# FPGA_Power.net
KiCad netlist of a schematic drawn in Altium Designer
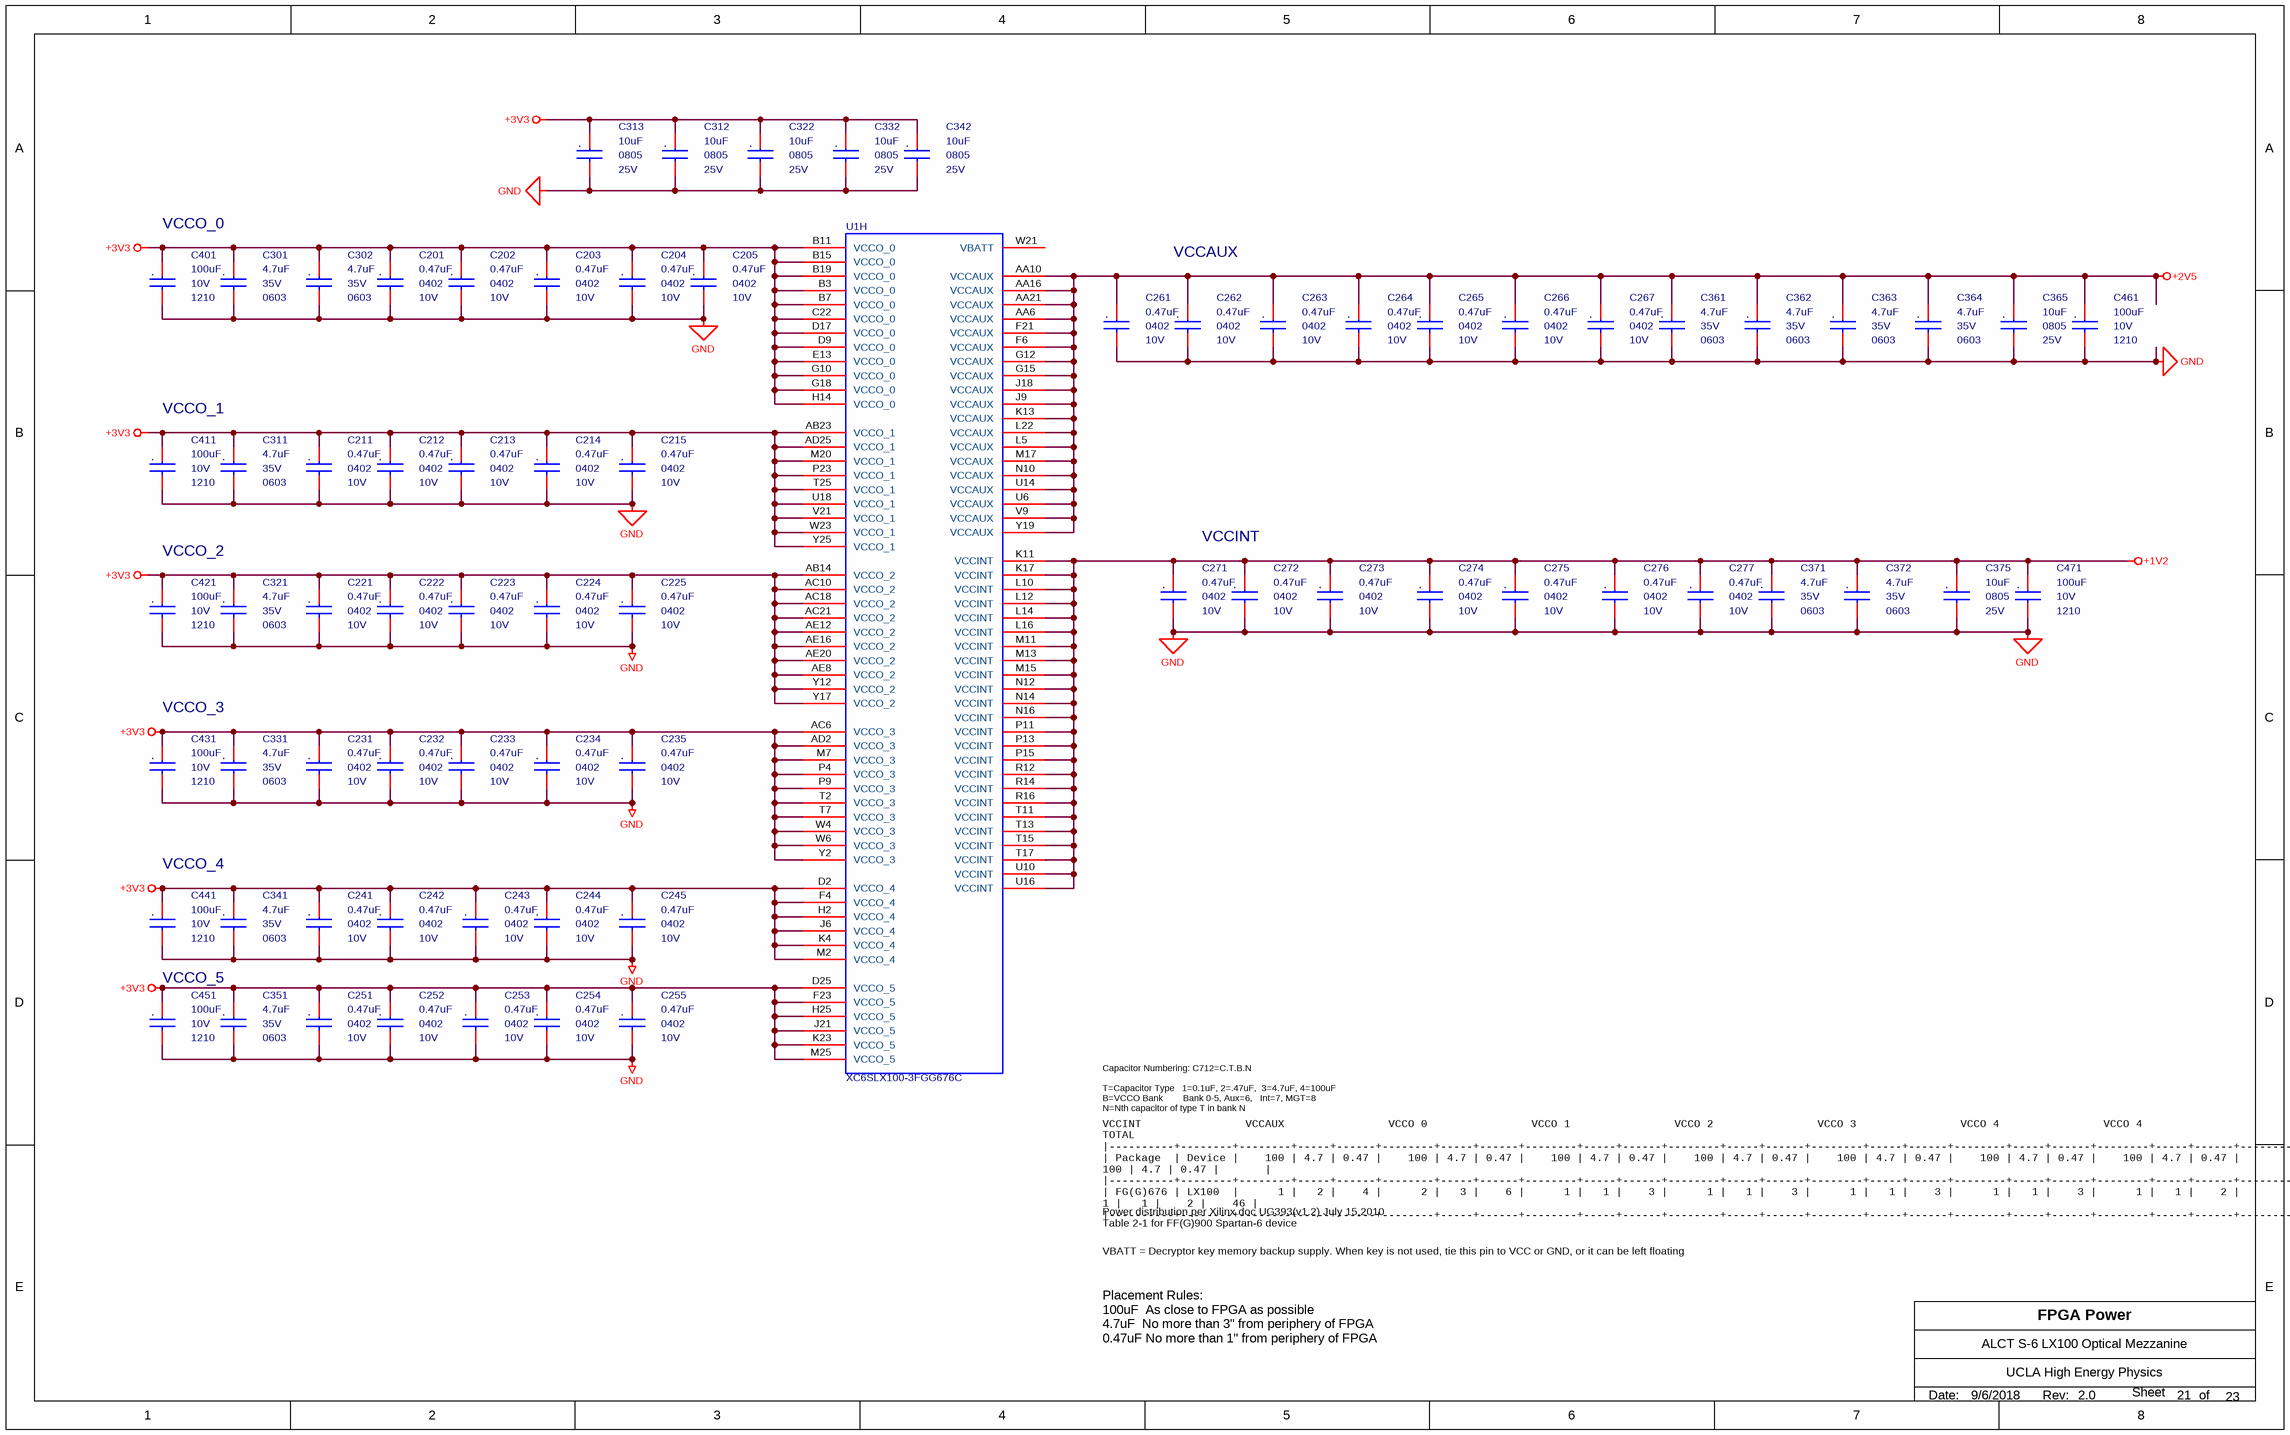
[diagram p0: FPGA_Power.SchDoc]

(export (version "E")
  (design (tool "Eeschema 10.0.6"))
  (components
    (comp (ref "C201")
      (value "0.47uF")
      (footprint "MC_S6/SM/C_0402_IPC")
      (description "CAP CER 0.47UF 10V X5R 0402")
      (fields
        (field (name "MANUFACTURER") "Murata Electronics North America")
        (field (name "MANUFACTURER PART NUMBER") "GRM155R61A474KE15D")
        (field (name "VOLTAGE - RATED") "10V")
        (field (name "PACKAGE") "0402")
      )
      (libsource (lib "ALCT_MEZ_SPARTAN6_Library") (part "GRM155R61A474KE15D"))
    )
    (comp (ref "C202")
      (value "0.47uF")
      (footprint "MC_S6/SM/C_0402_IPC")
      (description "CAP CER 0.47UF 10V X5R 0402")
      (fields
        (field (name "MANUFACTURER") "Murata Electronics North America")
        (field (name "MANUFACTURER PART NUMBER") "GRM155R61A474KE15D")
        (field (name "VOLTAGE - RATED") "10V")
        (field (name "PACKAGE") "0402")
      )
      (libsource (lib "ALCT_MEZ_SPARTAN6_Library") (part "GRM155R61A474KE15D"))
    )
    (comp (ref "C203")
      (value "0.47uF")
      (footprint "MC_S6/SM/C_0402_IPC")
      (description "CAP CER 0.47UF 10V X5R 0402")
      (fields
        (field (name "MANUFACTURER") "Murata Electronics North America")
        (field (name "MANUFACTURER PART NUMBER") "GRM155R61A474KE15D")
        (field (name "VOLTAGE - RATED") "10V")
        (field (name "PACKAGE") "0402")
      )
      (libsource (lib "ALCT_MEZ_SPARTAN6_Library") (part "GRM155R61A474KE15D"))
    )
    (comp (ref "C204")
      (value "0.47uF")
      (footprint "MC_S6/SM/C_0402_IPC")
      (description "CAP CER 0.47UF 10V X5R 0402")
      (fields
        (field (name "MANUFACTURER") "Murata Electronics North America")
        (field (name "MANUFACTURER PART NUMBER") "GRM155R61A474KE15D")
        (field (name "VOLTAGE - RATED") "10V")
        (field (name "PACKAGE") "0402")
      )
      (libsource (lib "ALCT_MEZ_SPARTAN6_Library") (part "GRM155R61A474KE15D"))
    )
    (comp (ref "C205")
      (value "0.47uF")
      (footprint "MC_S6/SM/C_0402_IPC")
      (description "CAP CER 0.47UF 10V X5R 0402")
      (fields
        (field (name "MANUFACTURER") "Murata Electronics North America")
        (field (name "MANUFACTURER PART NUMBER") "GRM155R61A474KE15D")
        (field (name "VOLTAGE - RATED") "10V")
        (field (name "PACKAGE") "0402")
      )
      (libsource (lib "ALCT_MEZ_SPARTAN6_Library") (part "GRM155R61A474KE15D"))
    )
    (comp (ref "C211")
      (value "0.47uF")
      (footprint "MC_S6/SM/C_0402_IPC")
      (description "CAP CER 0.47UF 10V X5R 0402")
      (fields
        (field (name "MANUFACTURER") "Murata Electronics North America")
        (field (name "MANUFACTURER PART NUMBER") "GRM155R61A474KE15D")
        (field (name "VOLTAGE - RATED") "10V")
        (field (name "PACKAGE") "0402")
      )
      (libsource (lib "ALCT_MEZ_SPARTAN6_Library") (part "GRM155R61A474KE15D"))
    )
    (comp (ref "C212")
      (value "0.47uF")
      (footprint "MC_S6/SM/C_0402_IPC")
      (description "CAP CER 0.47UF 10V X5R 0402")
      (fields
        (field (name "MANUFACTURER") "Murata Electronics North America")
        (field (name "MANUFACTURER PART NUMBER") "GRM155R61A474KE15D")
        (field (name "VOLTAGE - RATED") "10V")
        (field (name "PACKAGE") "0402")
      )
      (libsource (lib "ALCT_MEZ_SPARTAN6_Library") (part "GRM155R61A474KE15D"))
    )
    (comp (ref "C213")
      (value "0.47uF")
      (footprint "MC_S6/SM/C_0402_IPC")
      (description "CAP CER 0.47UF 10V X5R 0402")
      (fields
        (field (name "MANUFACTURER") "Murata Electronics North America")
        (field (name "MANUFACTURER PART NUMBER") "GRM155R61A474KE15D")
        (field (name "VOLTAGE - RATED") "10V")
        (field (name "PACKAGE") "0402")
      )
      (libsource (lib "ALCT_MEZ_SPARTAN6_Library") (part "GRM155R61A474KE15D"))
    )
    (comp (ref "C214")
      (value "0.47uF")
      (footprint "MC_S6/SM/C_0402_IPC")
      (description "CAP CER 0.47UF 10V X5R 0402")
      (fields
        (field (name "MANUFACTURER") "Murata Electronics North America")
        (field (name "MANUFACTURER PART NUMBER") "GRM155R61A474KE15D")
        (field (name "VOLTAGE - RATED") "10V")
        (field (name "PACKAGE") "0402")
      )
      (libsource (lib "ALCT_MEZ_SPARTAN6_Library") (part "GRM155R61A474KE15D"))
    )
    (comp (ref "C215")
      (value "0.47uF")
      (footprint "MC_S6/SM/C_0402_IPC")
      (description "CAP CER 0.47UF 10V X5R 0402")
      (fields
        (field (name "MANUFACTURER") "Murata Electronics North America")
        (field (name "MANUFACTURER PART NUMBER") "GRM155R61A474KE15D")
        (field (name "VOLTAGE - RATED") "10V")
        (field (name "PACKAGE") "0402")
      )
      (libsource (lib "ALCT_MEZ_SPARTAN6_Library") (part "GRM155R61A474KE15D"))
    )
    (comp (ref "C221")
      (value "0.47uF")
      (footprint "MC_S6/SM/C_0402_IPC")
      (description "CAP CER 0.47UF 10V X5R 0402")
      (fields
        (field (name "MANUFACTURER") "Murata Electronics North America")
        (field (name "MANUFACTURER PART NUMBER") "GRM155R61A474KE15D")
        (field (name "VOLTAGE - RATED") "10V")
        (field (name "PACKAGE") "0402")
      )
      (libsource (lib "ALCT_MEZ_SPARTAN6_Library") (part "GRM155R61A474KE15D"))
    )
    (comp (ref "C222")
      (value "0.47uF")
      (footprint "MC_S6/SM/C_0402_IPC")
      (description "CAP CER 0.47UF 10V X5R 0402")
      (fields
        (field (name "MANUFACTURER") "Murata Electronics North America")
        (field (name "MANUFACTURER PART NUMBER") "GRM155R61A474KE15D")
        (field (name "VOLTAGE - RATED") "10V")
        (field (name "PACKAGE") "0402")
      )
      (libsource (lib "ALCT_MEZ_SPARTAN6_Library") (part "GRM155R61A474KE15D"))
    )
    (comp (ref "C223")
      (value "0.47uF")
      (footprint "MC_S6/SM/C_0402_IPC")
      (description "CAP CER 0.47UF 10V X5R 0402")
      (fields
        (field (name "MANUFACTURER") "Murata Electronics North America")
        (field (name "MANUFACTURER PART NUMBER") "GRM155R61A474KE15D")
        (field (name "VOLTAGE - RATED") "10V")
        (field (name "PACKAGE") "0402")
      )
      (libsource (lib "ALCT_MEZ_SPARTAN6_Library") (part "GRM155R61A474KE15D"))
    )
    (comp (ref "C224")
      (value "0.47uF")
      (footprint "MC_S6/SM/C_0402_IPC")
      (description "CAP CER 0.47UF 10V X5R 0402")
      (fields
        (field (name "MANUFACTURER") "Murata Electronics North America")
        (field (name "MANUFACTURER PART NUMBER") "GRM155R61A474KE15D")
        (field (name "VOLTAGE - RATED") "10V")
        (field (name "PACKAGE") "0402")
      )
      (libsource (lib "ALCT_MEZ_SPARTAN6_Library") (part "GRM155R61A474KE15D"))
    )
    (comp (ref "C225")
      (value "0.47uF")
      (footprint "MC_S6/SM/C_0402_IPC")
      (description "CAP CER 0.47UF 10V X5R 0402")
      (fields
        (field (name "MANUFACTURER") "Murata Electronics North America")
        (field (name "MANUFACTURER PART NUMBER") "GRM155R61A474KE15D")
        (field (name "VOLTAGE - RATED") "10V")
        (field (name "PACKAGE") "0402")
      )
      (libsource (lib "ALCT_MEZ_SPARTAN6_Library") (part "GRM155R61A474KE15D"))
    )
    (comp (ref "C231")
      (value "0.47uF")
      (footprint "MC_S6/SM/C_0402_IPC")
      (description "CAP CER 0.47UF 10V X5R 0402")
      (fields
        (field (name "MANUFACTURER") "Murata Electronics North America")
        (field (name "MANUFACTURER PART NUMBER") "GRM155R61A474KE15D")
        (field (name "VOLTAGE - RATED") "10V")
        (field (name "PACKAGE") "0402")
      )
      (libsource (lib "ALCT_MEZ_SPARTAN6_Library") (part "GRM155R61A474KE15D"))
    )
    (comp (ref "C232")
      (value "0.47uF")
      (footprint "MC_S6/SM/C_0402_IPC")
      (description "CAP CER 0.47UF 10V X5R 0402")
      (fields
        (field (name "MANUFACTURER") "Murata Electronics North America")
        (field (name "MANUFACTURER PART NUMBER") "GRM155R61A474KE15D")
        (field (name "VOLTAGE - RATED") "10V")
        (field (name "PACKAGE") "0402")
      )
      (libsource (lib "ALCT_MEZ_SPARTAN6_Library") (part "GRM155R61A474KE15D"))
    )
    (comp (ref "C233")
      (value "0.47uF")
      (footprint "MC_S6/SM/C_0402_IPC")
      (description "CAP CER 0.47UF 10V X5R 0402")
      (fields
        (field (name "MANUFACTURER") "Murata Electronics North America")
        (field (name "MANUFACTURER PART NUMBER") "GRM155R61A474KE15D")
        (field (name "VOLTAGE - RATED") "10V")
        (field (name "PACKAGE") "0402")
      )
      (libsource (lib "ALCT_MEZ_SPARTAN6_Library") (part "GRM155R61A474KE15D"))
    )
    (comp (ref "C234")
      (value "0.47uF")
      (footprint "MC_S6/SM/C_0402_IPC")
      (description "CAP CER 0.47UF 10V X5R 0402")
      (fields
        (field (name "MANUFACTURER") "Murata Electronics North America")
        (field (name "MANUFACTURER PART NUMBER") "GRM155R61A474KE15D")
        (field (name "VOLTAGE - RATED") "10V")
        (field (name "PACKAGE") "0402")
      )
      (libsource (lib "ALCT_MEZ_SPARTAN6_Library") (part "GRM155R61A474KE15D"))
    )
    (comp (ref "C235")
      (value "0.47uF")
      (footprint "MC_S6/SM/C_0402_IPC")
      (description "CAP CER 0.47UF 10V X5R 0402")
      (fields
        (field (name "MANUFACTURER") "Murata Electronics North America")
        (field (name "MANUFACTURER PART NUMBER") "GRM155R61A474KE15D")
        (field (name "VOLTAGE - RATED") "10V")
        (field (name "PACKAGE") "0402")
      )
      (libsource (lib "ALCT_MEZ_SPARTAN6_Library") (part "GRM155R61A474KE15D"))
    )
    (comp (ref "C241")
      (value "0.47uF")
      (footprint "MC_S6/SM/C_0402_IPC")
      (description "CAP CER 0.47UF 10V X5R 0402")
      (fields
        (field (name "MANUFACTURER") "Murata Electronics North America")
        (field (name "MANUFACTURER PART NUMBER") "GRM155R61A474KE15D")
        (field (name "VOLTAGE - RATED") "10V")
        (field (name "PACKAGE") "0402")
      )
      (libsource (lib "ALCT_MEZ_SPARTAN6_Library") (part "GRM155R61A474KE15D"))
    )
    (comp (ref "C242")
      (value "0.47uF")
      (footprint "MC_S6/SM/C_0402_IPC")
      (description "CAP CER 0.47UF 10V X5R 0402")
      (fields
        (field (name "MANUFACTURER") "Murata Electronics North America")
        (field (name "MANUFACTURER PART NUMBER") "GRM155R61A474KE15D")
        (field (name "VOLTAGE - RATED") "10V")
        (field (name "PACKAGE") "0402")
      )
      (libsource (lib "ALCT_MEZ_SPARTAN6_Library") (part "GRM155R61A474KE15D"))
    )
    (comp (ref "C243")
      (value "0.47uF")
      (footprint "MC_S6/SM/C_0402_IPC")
      (description "CAP CER 0.47UF 10V X5R 0402")
      (fields
        (field (name "MANUFACTURER") "Murata Electronics North America")
        (field (name "MANUFACTURER PART NUMBER") "GRM155R61A474KE15D")
        (field (name "VOLTAGE - RATED") "10V")
        (field (name "PACKAGE") "0402")
      )
      (libsource (lib "ALCT_MEZ_SPARTAN6_Library") (part "GRM155R61A474KE15D"))
    )
    (comp (ref "C244")
      (value "0.47uF")
      (footprint "MC_S6/SM/C_0402_IPC")
      (description "CAP CER 0.47UF 10V X5R 0402")
      (fields
        (field (name "MANUFACTURER") "Murata Electronics North America")
        (field (name "MANUFACTURER PART NUMBER") "GRM155R61A474KE15D")
        (field (name "VOLTAGE - RATED") "10V")
        (field (name "PACKAGE") "0402")
      )
      (libsource (lib "ALCT_MEZ_SPARTAN6_Library") (part "GRM155R61A474KE15D"))
    )
    (comp (ref "C245")
      (value "0.47uF")
      (footprint "MC_S6/SM/C_0402_IPC")
      (description "CAP CER 0.47UF 10V X5R 0402")
      (fields
        (field (name "MANUFACTURER") "Murata Electronics North America")
        (field (name "MANUFACTURER PART NUMBER") "GRM155R61A474KE15D")
        (field (name "VOLTAGE - RATED") "10V")
        (field (name "PACKAGE") "0402")
      )
      (libsource (lib "ALCT_MEZ_SPARTAN6_Library") (part "GRM155R61A474KE15D"))
    )
    (comp (ref "C251")
      (value "0.47uF")
      (footprint "MC_S6/SM/C_0402_IPC")
      (description "CAP CER 0.47UF 10V X5R 0402")
      (fields
        (field (name "MANUFACTURER") "Murata Electronics North America")
        (field (name "MANUFACTURER PART NUMBER") "GRM155R61A474KE15D")
        (field (name "VOLTAGE - RATED") "10V")
        (field (name "PACKAGE") "0402")
      )
      (libsource (lib "ALCT_MEZ_SPARTAN6_Library") (part "GRM155R61A474KE15D"))
    )
    (comp (ref "C252")
      (value "0.47uF")
      (footprint "MC_S6/SM/C_0402_IPC")
      (description "CAP CER 0.47UF 10V X5R 0402")
      (fields
        (field (name "MANUFACTURER") "Murata Electronics North America")
        (field (name "MANUFACTURER PART NUMBER") "GRM155R61A474KE15D")
        (field (name "VOLTAGE - RATED") "10V")
        (field (name "PACKAGE") "0402")
      )
      (libsource (lib "ALCT_MEZ_SPARTAN6_Library") (part "GRM155R61A474KE15D"))
    )
    (comp (ref "C253")
      (value "0.47uF")
      (footprint "MC_S6/SM/C_0402_IPC")
      (description "CAP CER 0.47UF 10V X5R 0402")
      (fields
        (field (name "MANUFACTURER") "Murata Electronics North America")
        (field (name "MANUFACTURER PART NUMBER") "GRM155R61A474KE15D")
        (field (name "VOLTAGE - RATED") "10V")
        (field (name "PACKAGE") "0402")
      )
      (libsource (lib "ALCT_MEZ_SPARTAN6_Library") (part "GRM155R61A474KE15D"))
    )
    (comp (ref "C254")
      (value "0.47uF")
      (footprint "MC_S6/SM/C_0402_IPC")
      (description "CAP CER 0.47UF 10V X5R 0402")
      (fields
        (field (name "MANUFACTURER") "Murata Electronics North America")
        (field (name "MANUFACTURER PART NUMBER") "GRM155R61A474KE15D")
        (field (name "VOLTAGE - RATED") "10V")
        (field (name "PACKAGE") "0402")
      )
      (libsource (lib "ALCT_MEZ_SPARTAN6_Library") (part "GRM155R61A474KE15D"))
    )
    (comp (ref "C255")
      (value "0.47uF")
      (footprint "MC_S6/SM/C_0402_IPC")
      (description "CAP CER 0.47UF 10V X5R 0402")
      (fields
        (field (name "MANUFACTURER") "Murata Electronics North America")
        (field (name "MANUFACTURER PART NUMBER") "GRM155R61A474KE15D")
        (field (name "VOLTAGE - RATED") "10V")
        (field (name "PACKAGE") "0402")
      )
      (libsource (lib "ALCT_MEZ_SPARTAN6_Library") (part "GRM155R61A474KE15D"))
    )
    (comp (ref "C261")
      (value "0.47uF")
      (footprint "MC_S6/SM/C_0402_IPC")
      (description "CAP CER 0.47UF 10V X5R 0402")
      (fields
        (field (name "MANUFACTURER") "Murata Electronics North America")
        (field (name "MANUFACTURER PART NUMBER") "GRM155R61A474KE15D")
        (field (name "VOLTAGE - RATED") "10V")
        (field (name "PACKAGE") "0402")
      )
      (libsource (lib "ALCT_MEZ_SPARTAN6_Library") (part "GRM155R61A474KE15D"))
    )
    (comp (ref "C262")
      (value "0.47uF")
      (footprint "MC_S6/SM/C_0402_IPC")
      (description "CAP CER 0.47UF 10V X5R 0402")
      (fields
        (field (name "MANUFACTURER") "Murata Electronics North America")
        (field (name "MANUFACTURER PART NUMBER") "GRM155R61A474KE15D")
        (field (name "VOLTAGE - RATED") "10V")
        (field (name "PACKAGE") "0402")
      )
      (libsource (lib "ALCT_MEZ_SPARTAN6_Library") (part "GRM155R61A474KE15D"))
    )
    (comp (ref "C263")
      (value "0.47uF")
      (footprint "MC_S6/SM/C_0402_IPC")
      (description "CAP CER 0.47UF 10V X5R 0402")
      (fields
        (field (name "MANUFACTURER") "Murata Electronics North America")
        (field (name "MANUFACTURER PART NUMBER") "GRM155R61A474KE15D")
        (field (name "VOLTAGE - RATED") "10V")
        (field (name "PACKAGE") "0402")
      )
      (libsource (lib "ALCT_MEZ_SPARTAN6_Library") (part "GRM155R61A474KE15D"))
    )
    (comp (ref "C264")
      (value "0.47uF")
      (footprint "MC_S6/SM/C_0402_IPC")
      (description "CAP CER 0.47UF 10V X5R 0402")
      (fields
        (field (name "MANUFACTURER") "Murata Electronics North America")
        (field (name "MANUFACTURER PART NUMBER") "GRM155R61A474KE15D")
        (field (name "VOLTAGE - RATED") "10V")
        (field (name "PACKAGE") "0402")
      )
      (libsource (lib "ALCT_MEZ_SPARTAN6_Library") (part "GRM155R61A474KE15D"))
    )
    (comp (ref "C265")
      (value "0.47uF")
      (footprint "MC_S6/SM/C_0402_IPC")
      (description "CAP CER 0.47UF 10V X5R 0402")
      (fields
        (field (name "MANUFACTURER") "Murata Electronics North America")
        (field (name "MANUFACTURER PART NUMBER") "GRM155R61A474KE15D")
        (field (name "VOLTAGE - RATED") "10V")
        (field (name "PACKAGE") "0402")
      )
      (libsource (lib "ALCT_MEZ_SPARTAN6_Library") (part "GRM155R61A474KE15D"))
    )
    (comp (ref "C266")
      (value "0.47uF")
      (footprint "MC_S6/SM/C_0402_IPC")
      (description "CAP CER 0.47UF 10V X5R 0402")
      (fields
        (field (name "MANUFACTURER") "Murata Electronics North America")
        (field (name "MANUFACTURER PART NUMBER") "GRM155R61A474KE15D")
        (field (name "VOLTAGE - RATED") "10V")
        (field (name "PACKAGE") "0402")
      )
      (libsource (lib "ALCT_MEZ_SPARTAN6_Library") (part "GRM155R61A474KE15D"))
    )
    (comp (ref "C267")
      (value "0.47uF")
      (footprint "MC_S6/SM/C_0402_IPC")
      (description "CAP CER 0.47UF 10V X5R 0402")
      (fields
        (field (name "MANUFACTURER") "Murata Electronics North America")
        (field (name "MANUFACTURER PART NUMBER") "GRM155R61A474KE15D")
        (field (name "VOLTAGE - RATED") "10V")
        (field (name "PACKAGE") "0402")
      )
      (libsource (lib "ALCT_MEZ_SPARTAN6_Library") (part "GRM155R61A474KE15D"))
    )
    (comp (ref "C271")
      (value "0.47uF")
      (footprint "MC_S6/SM/C_0402_IPC")
      (description "CAP CER 0.47UF 10V X5R 0402")
      (fields
        (field (name "MANUFACTURER") "Murata Electronics North America")
        (field (name "MANUFACTURER PART NUMBER") "GRM155R61A474KE15D")
        (field (name "VOLTAGE - RATED") "10V")
        (field (name "PACKAGE") "0402")
      )
      (libsource (lib "ALCT_MEZ_SPARTAN6_Library") (part "GRM155R61A474KE15D"))
    )
    (comp (ref "C272")
      (value "0.47uF")
      (footprint "MC_S6/SM/C_0402_IPC")
      (description "CAP CER 0.47UF 10V X5R 0402")
      (fields
        (field (name "MANUFACTURER") "Murata Electronics North America")
        (field (name "MANUFACTURER PART NUMBER") "GRM155R61A474KE15D")
        (field (name "VOLTAGE - RATED") "10V")
        (field (name "PACKAGE") "0402")
      )
      (libsource (lib "ALCT_MEZ_SPARTAN6_Library") (part "GRM155R61A474KE15D"))
    )
    (comp (ref "C273")
      (value "0.47uF")
      (footprint "MC_S6/SM/C_0402_IPC")
      (description "CAP CER 0.47UF 10V X5R 0402")
      (fields
        (field (name "MANUFACTURER") "Murata Electronics North America")
        (field (name "MANUFACTURER PART NUMBER") "GRM155R61A474KE15D")
        (field (name "VOLTAGE - RATED") "10V")
        (field (name "PACKAGE") "0402")
      )
      (libsource (lib "ALCT_MEZ_SPARTAN6_Library") (part "GRM155R61A474KE15D"))
    )
    (comp (ref "C274")
      (value "0.47uF")
      (footprint "MC_S6/SM/C_0402_IPC")
      (description "CAP CER 0.47UF 10V X5R 0402")
      (fields
        (field (name "MANUFACTURER") "Murata Electronics North America")
        (field (name "MANUFACTURER PART NUMBER") "GRM155R61A474KE15D")
        (field (name "VOLTAGE - RATED") "10V")
        (field (name "PACKAGE") "0402")
      )
      (libsource (lib "ALCT_MEZ_SPARTAN6_Library") (part "GRM155R61A474KE15D"))
    )
    (comp (ref "C275")
      (value "0.47uF")
      (footprint "MC_S6/SM/C_0402_IPC")
      (description "CAP CER 0.47UF 10V X5R 0402")
      (fields
        (field (name "MANUFACTURER") "Murata Electronics North America")
        (field (name "MANUFACTURER PART NUMBER") "GRM155R61A474KE15D")
        (field (name "VOLTAGE - RATED") "10V")
        (field (name "PACKAGE") "0402")
      )
      (libsource (lib "ALCT_MEZ_SPARTAN6_Library") (part "GRM155R61A474KE15D"))
    )
    (comp (ref "C276")
      (value "0.47uF")
      (footprint "MC_S6/SM/C_0402_IPC")
      (description "CAP CER 0.47UF 10V X5R 0402")
      (fields
        (field (name "MANUFACTURER") "Murata Electronics North America")
        (field (name "MANUFACTURER PART NUMBER") "GRM155R61A474KE15D")
        (field (name "VOLTAGE - RATED") "10V")
        (field (name "PACKAGE") "0402")
      )
      (libsource (lib "ALCT_MEZ_SPARTAN6_Library") (part "GRM155R61A474KE15D"))
    )
    (comp (ref "C277")
      (value "0.47uF")
      (footprint "MC_S6/SM/C_0402_IPC")
      (description "CAP CER 0.47UF 10V X5R 0402")
      (fields
        (field (name "MANUFACTURER") "Murata Electronics North America")
        (field (name "MANUFACTURER PART NUMBER") "GRM155R61A474KE15D")
        (field (name "VOLTAGE - RATED") "10V")
        (field (name "PACKAGE") "0402")
      )
      (libsource (lib "ALCT_MEZ_SPARTAN6_Library") (part "GRM155R61A474KE15D"))
    )
    (comp (ref "C301")
      (value "4.7uF")
      (footprint "MC_S6/SM/C_0603_IPC")
      (description "CAP CER 4.7UF 35V X5R 0603")
      (fields
        (field (name "MANUFACTURER") "Murata")
        (field (name "MANUFACTURER PART NUMBER") "GRM188R6YA475KE15D")
        (field (name "VOLTAGE - RATED") "35V")
        (field (name "PACKAGE") "0603")
      )
      (libsource (lib "ALCT_MEZ_SPARTAN6_Library") (part "GRM188R6YA475KE15D"))
    )
    (comp (ref "C302")
      (value "4.7uF")
      (footprint "MC_S6/SM/C_0603_IPC")
      (description "CAP CER 4.7UF 35V X5R 0603")
      (fields
        (field (name "MANUFACTURER") "Murata")
        (field (name "MANUFACTURER PART NUMBER") "GRM188R6YA475KE15D")
        (field (name "VOLTAGE - RATED") "35V")
        (field (name "PACKAGE") "0603")
      )
      (libsource (lib "ALCT_MEZ_SPARTAN6_Library") (part "GRM188R6YA475KE15D"))
    )
    (comp (ref "C311")
      (value "4.7uF")
      (footprint "MC_S6/SM/C_0603_IPC")
      (description "CAP CER 4.7UF 35V X5R 0603")
      (fields
        (field (name "MANUFACTURER") "Murata")
        (field (name "MANUFACTURER PART NUMBER") "GRM188R6YA475KE15D")
        (field (name "VOLTAGE - RATED") "35V")
        (field (name "PACKAGE") "0603")
      )
      (libsource (lib "ALCT_MEZ_SPARTAN6_Library") (part "GRM188R6YA475KE15D"))
    )
    (comp (ref "C312")
      (value "10uF")
      (footprint "MC_S6/SM/C_0805_IPC")
      (description "CAP CER 10UF 25V X5R 0805")
      (fields
        (field (name "MANUFACTURER") "Murata Electronics North America")
        (field (name "MANUFACTURER PART NUMBER") "GRM21BR61E106KA73L")
        (field (name "VOLTAGE - RATED") "25V")
        (field (name "PACKAGE") "0805")
      )
      (libsource (lib "ALCT_MEZ_SPARTAN6_Library") (part "GRM21BR61E106KA73L"))
    )
    (comp (ref "C313")
      (value "10uF")
      (footprint "MC_S6/SM/C_0805_IPC")
      (description "CAP CER 10UF 25V X5R 0805")
      (fields
        (field (name "MANUFACTURER") "Murata Electronics North America")
        (field (name "MANUFACTURER PART NUMBER") "GRM21BR61E106KA73L")
        (field (name "VOLTAGE - RATED") "25V")
        (field (name "PACKAGE") "0805")
      )
      (libsource (lib "ALCT_MEZ_SPARTAN6_Library") (part "GRM21BR61E106KA73L"))
    )
    (comp (ref "C321")
      (value "4.7uF")
      (footprint "MC_S6/SM/C_0603_IPC")
      (description "CAP CER 4.7UF 35V X5R 0603")
      (fields
        (field (name "MANUFACTURER") "Murata")
        (field (name "MANUFACTURER PART NUMBER") "GRM188R6YA475KE15D")
        (field (name "VOLTAGE - RATED") "35V")
        (field (name "PACKAGE") "0603")
      )
      (libsource (lib "ALCT_MEZ_SPARTAN6_Library") (part "GRM188R6YA475KE15D"))
    )
    (comp (ref "C322")
      (value "10uF")
      (footprint "MC_S6/SM/C_0805_IPC")
      (description "CAP CER 10UF 25V X5R 0805")
      (fields
        (field (name "MANUFACTURER") "Murata Electronics North America")
        (field (name "MANUFACTURER PART NUMBER") "GRM21BR61E106KA73L")
        (field (name "VOLTAGE - RATED") "25V")
        (field (name "PACKAGE") "0805")
      )
      (libsource (lib "ALCT_MEZ_SPARTAN6_Library") (part "GRM21BR61E106KA73L"))
    )
    (comp (ref "C331")
      (value "4.7uF")
      (footprint "MC_S6/SM/C_0603_IPC")
      (description "CAP CER 4.7UF 35V X5R 0603")
      (fields
        (field (name "MANUFACTURER") "Murata")
        (field (name "MANUFACTURER PART NUMBER") "GRM188R6YA475KE15D")
        (field (name "VOLTAGE - RATED") "35V")
        (field (name "PACKAGE") "0603")
      )
      (libsource (lib "ALCT_MEZ_SPARTAN6_Library") (part "GRM188R6YA475KE15D"))
    )
    (comp (ref "C332")
      (value "10uF")
      (footprint "MC_S6/SM/C_0805_IPC")
      (description "CAP CER 10UF 25V X5R 0805")
      (fields
        (field (name "MANUFACTURER") "Murata Electronics North America")
        (field (name "MANUFACTURER PART NUMBER") "GRM21BR61E106KA73L")
        (field (name "VOLTAGE - RATED") "25V")
        (field (name "PACKAGE") "0805")
      )
      (libsource (lib "ALCT_MEZ_SPARTAN6_Library") (part "GRM21BR61E106KA73L"))
    )
    (comp (ref "C341")
      (value "4.7uF")
      (footprint "MC_S6/SM/C_0603_IPC")
      (description "CAP CER 4.7UF 35V X5R 0603")
      (fields
        (field (name "MANUFACTURER") "Murata")
        (field (name "MANUFACTURER PART NUMBER") "GRM188R6YA475KE15D")
        (field (name "VOLTAGE - RATED") "35V")
        (field (name "PACKAGE") "0603")
      )
      (libsource (lib "ALCT_MEZ_SPARTAN6_Library") (part "GRM188R6YA475KE15D"))
    )
    (comp (ref "C342")
      (value "10uF")
      (footprint "MC_S6/SM/C_0805_IPC")
      (description "CAP CER 10UF 25V X5R 0805")
      (fields
        (field (name "MANUFACTURER") "Murata Electronics North America")
        (field (name "MANUFACTURER PART NUMBER") "GRM21BR61E106KA73L")
        (field (name "VOLTAGE - RATED") "25V")
        (field (name "PACKAGE") "0805")
      )
      (libsource (lib "ALCT_MEZ_SPARTAN6_Library") (part "GRM21BR61E106KA73L"))
    )
    (comp (ref "C351")
      (value "4.7uF")
      (footprint "MC_S6/SM/C_0603_IPC")
      (description "CAP CER 4.7UF 35V X5R 0603")
      (fields
        (field (name "MANUFACTURER") "Murata")
        (field (name "MANUFACTURER PART NUMBER") "GRM188R6YA475KE15D")
        (field (name "VOLTAGE - RATED") "35V")
        (field (name "PACKAGE") "0603")
      )
      (libsource (lib "ALCT_MEZ_SPARTAN6_Library") (part "GRM188R6YA475KE15D"))
    )
    (comp (ref "C361")
      (value "4.7uF")
      (footprint "MC_S6/SM/C_0603_IPC")
      (description "CAP CER 4.7UF 35V X5R 0603")
      (fields
        (field (name "MANUFACTURER") "Murata")
        (field (name "MANUFACTURER PART NUMBER") "GRM188R6YA475KE15D")
        (field (name "VOLTAGE - RATED") "35V")
        (field (name "PACKAGE") "0603")
      )
      (libsource (lib "ALCT_MEZ_SPARTAN6_Library") (part "GRM188R6YA475KE15D"))
    )
    (comp (ref "C362")
      (value "4.7uF")
      (footprint "MC_S6/SM/C_0603_IPC")
      (description "CAP CER 4.7UF 35V X5R 0603")
      (fields
        (field (name "MANUFACTURER") "Murata")
        (field (name "MANUFACTURER PART NUMBER") "GRM188R6YA475KE15D")
        (field (name "VOLTAGE - RATED") "35V")
        (field (name "PACKAGE") "0603")
      )
      (libsource (lib "ALCT_MEZ_SPARTAN6_Library") (part "GRM188R6YA475KE15D"))
    )
    (comp (ref "C363")
      (value "4.7uF")
      (footprint "MC_S6/SM/C_0603_IPC")
      (description "CAP CER 4.7UF 35V X5R 0603")
      (fields
        (field (name "MANUFACTURER") "Murata")
        (field (name "MANUFACTURER PART NUMBER") "GRM188R6YA475KE15D")
        (field (name "VOLTAGE - RATED") "35V")
        (field (name "PACKAGE") "0603")
      )
      (libsource (lib "ALCT_MEZ_SPARTAN6_Library") (part "GRM188R6YA475KE15D"))
    )
    (comp (ref "C364")
      (value "4.7uF")
      (footprint "MC_S6/SM/C_0603_IPC")
      (description "CAP CER 4.7UF 35V X5R 0603")
      (fields
        (field (name "MANUFACTURER") "Murata")
        (field (name "MANUFACTURER PART NUMBER") "GRM188R6YA475KE15D")
        (field (name "VOLTAGE - RATED") "35V")
        (field (name "PACKAGE") "0603")
      )
      (libsource (lib "ALCT_MEZ_SPARTAN6_Library") (part "GRM188R6YA475KE15D"))
    )
    (comp (ref "C365")
      (value "10uF")
      (footprint "MC_S6/SM/C_0805_IPC")
      (description "CAP CER 10UF 25V X5R 0805")
      (fields
        (field (name "MANUFACTURER") "Murata Electronics North America")
        (field (name "MANUFACTURER PART NUMBER") "GRM21BR61E106KA73L")
        (field (name "VOLTAGE - RATED") "25V")
        (field (name "PACKAGE") "0805")
      )
      (libsource (lib "ALCT_MEZ_SPARTAN6_Library") (part "GRM21BR61E106KA73L"))
    )
    (comp (ref "C371")
      (value "4.7uF")
      (footprint "MC_S6/SM/C_0603_IPC")
      (description "CAP CER 4.7UF 35V X5R 0603")
      (fields
        (field (name "MANUFACTURER") "Murata")
        (field (name "MANUFACTURER PART NUMBER") "GRM188R6YA475KE15D")
        (field (name "VOLTAGE - RATED") "35V")
        (field (name "PACKAGE") "0603")
      )
      (libsource (lib "ALCT_MEZ_SPARTAN6_Library") (part "GRM188R6YA475KE15D"))
    )
    (comp (ref "C372")
      (value "4.7uF")
      (footprint "MC_S6/SM/C_0603_IPC")
      (description "CAP CER 4.7UF 35V X5R 0603")
      (fields
        (field (name "MANUFACTURER") "Murata")
        (field (name "MANUFACTURER PART NUMBER") "GRM188R6YA475KE15D")
        (field (name "VOLTAGE - RATED") "35V")
        (field (name "PACKAGE") "0603")
      )
      (libsource (lib "ALCT_MEZ_SPARTAN6_Library") (part "GRM188R6YA475KE15D"))
    )
    (comp (ref "C375")
      (value "10uF")
      (footprint "MC_S6/SM/C_0805_IPC")
      (description "CAP CER 10UF 25V X5R 0805")
      (fields
        (field (name "MANUFACTURER") "Murata Electronics North America")
        (field (name "MANUFACTURER PART NUMBER") "GRM21BR61E106KA73L")
        (field (name "VOLTAGE - RATED") "25V")
        (field (name "PACKAGE") "0805")
      )
      (libsource (lib "ALCT_MEZ_SPARTAN6_Library") (part "GRM21BR61E106KA73L"))
    )
    (comp (ref "C401")
      (value "100uF")
      (footprint "MC_S6/SM/C_1210_IPC")
      (description "CAP CER 100UF 10V X5R 1210")
      (fields
        (field (name "MANUFACTURER") "Taiyo Yuden")
        (field (name "MANUFACTURER PART NUMBER") "LMK325BJ107MM-T")
        (field (name "VOLTAGE - RATED") "10V")
        (field (name "PACKAGE") "1210")
      )
      (libsource (lib "ALCT_MEZ_SPARTAN6_Library") (part "LMK325BJ107MM-T"))
    )
    (comp (ref "C411")
      (value "100uF")
      (footprint "MC_S6/SM/C_1210_IPC")
      (description "CAP CER 100UF 10V X5R 1210")
      (fields
        (field (name "MANUFACTURER") "Taiyo Yuden")
        (field (name "MANUFACTURER PART NUMBER") "LMK325BJ107MM-T")
        (field (name "VOLTAGE - RATED") "10V")
        (field (name "PACKAGE") "1210")
      )
      (libsource (lib "ALCT_MEZ_SPARTAN6_Library") (part "LMK325BJ107MM-T"))
    )
    (comp (ref "C421")
      (value "100uF")
      (footprint "MC_S6/SM/C_1210_IPC")
      (description "CAP CER 100UF 10V X5R 1210")
      (fields
        (field (name "MANUFACTURER") "Taiyo Yuden")
        (field (name "MANUFACTURER PART NUMBER") "LMK325BJ107MM-T")
        (field (name "VOLTAGE - RATED") "10V")
        (field (name "PACKAGE") "1210")
      )
      (libsource (lib "ALCT_MEZ_SPARTAN6_Library") (part "LMK325BJ107MM-T"))
    )
    (comp (ref "C431")
      (value "100uF")
      (footprint "MC_S6/SM/C_1210_IPC")
      (description "CAP CER 100UF 10V X5R 1210")
      (fields
        (field (name "MANUFACTURER") "Taiyo Yuden")
        (field (name "MANUFACTURER PART NUMBER") "LMK325BJ107MM-T")
        (field (name "VOLTAGE - RATED") "10V")
        (field (name "PACKAGE") "1210")
      )
      (libsource (lib "ALCT_MEZ_SPARTAN6_Library") (part "LMK325BJ107MM-T"))
    )
    (comp (ref "C441")
      (value "100uF")
      (footprint "MC_S6/SM/C_1210_IPC")
      (description "CAP CER 100UF 10V X5R 1210")
      (fields
        (field (name "MANUFACTURER") "Taiyo Yuden")
        (field (name "MANUFACTURER PART NUMBER") "LMK325BJ107MM-T")
        (field (name "VOLTAGE - RATED") "10V")
        (field (name "PACKAGE") "1210")
      )
      (libsource (lib "ALCT_MEZ_SPARTAN6_Library") (part "LMK325BJ107MM-T"))
    )
    (comp (ref "C451")
      (value "100uF")
      (footprint "MC_S6/SM/C_1210_IPC")
      (description "CAP CER 100UF 10V X5R 1210")
      (fields
        (field (name "MANUFACTURER") "Taiyo Yuden")
        (field (name "MANUFACTURER PART NUMBER") "LMK325BJ107MM-T")
        (field (name "VOLTAGE - RATED") "10V")
        (field (name "PACKAGE") "1210")
      )
      (libsource (lib "ALCT_MEZ_SPARTAN6_Library") (part "LMK325BJ107MM-T"))
    )
    (comp (ref "C461")
      (value "100uF")
      (footprint "MC_S6/SM/C_1210_IPC")
      (description "CAP CER 100UF 10V X5R 1210")
      (fields
        (field (name "MANUFACTURER") "Taiyo Yuden")
        (field (name "MANUFACTURER PART NUMBER") "LMK325BJ107MM-T")
        (field (name "VOLTAGE - RATED") "10V")
        (field (name "PACKAGE") "1210")
      )
      (libsource (lib "ALCT_MEZ_SPARTAN6_Library") (part "LMK325BJ107MM-T"))
    )
    (comp (ref "C471")
      (value "100uF")
      (footprint "MC_S6/SM/C_1210_IPC")
      (description "CAP CER 100UF 10V X5R 1210")
      (fields
        (field (name "MANUFACTURER") "Taiyo Yuden")
        (field (name "MANUFACTURER PART NUMBER") "LMK325BJ107MM-T")
        (field (name "VOLTAGE - RATED") "10V")
        (field (name "PACKAGE") "1210")
      )
      (libsource (lib "ALCT_MEZ_SPARTAN6_Library") (part "LMK325BJ107MM-T"))
    )
    (comp (ref "U1")
      (value "XC6SLX100-3FGG676C")
      (footprint "FGG676")
      (fields (field (name "MANUFACTURER") "Xilinx Inc."))
      (libsource (lib "ALCT_MEZ_SPARTAN6_Library") (part "XC6SLX100-3FGG676C"))
    )
  )
  (nets
    (net (code "1") (name "+1V2") (class "Default")
      (node (ref "C271") (pin "1") (pinfunction "1_1") (pintype "passive"))
      (node (ref "C272") (pin "1") (pinfunction "1_1") (pintype "passive"))
      (node (ref "C273") (pin "1") (pinfunction "1_1") (pintype "passive"))
      (node (ref "C274") (pin "1") (pinfunction "1_1") (pintype "passive"))
      (node (ref "C275") (pin "1") (pinfunction "1_1") (pintype "passive"))
      (node (ref "C276") (pin "1") (pinfunction "1_1") (pintype "passive"))
      (node (ref "C277") (pin "1") (pinfunction "1_1") (pintype "passive"))
      (node (ref "C371") (pin "1") (pinfunction "1_1") (pintype "passive"))
      (node (ref "C372") (pin "1") (pinfunction "1_1") (pintype "passive"))
      (node (ref "C375") (pin "1") (pinfunction "1_1") (pintype "passive"))
      (node (ref "C471") (pin "1") (pinfunction "1_1") (pintype "passive"))
      (node (ref "U1") (pin "K11") (pinfunction "VCCINT_K11") (pintype "power_in"))
      (node (ref "U1") (pin "K17") (pinfunction "VCCINT_K17") (pintype "power_in"))
      (node (ref "U1") (pin "L10") (pinfunction "VCCINT_L10") (pintype "power_in"))
      (node (ref "U1") (pin "L12") (pinfunction "VCCINT_L12") (pintype "power_in"))
      (node (ref "U1") (pin "L14") (pinfunction "VCCINT_L14") (pintype "power_in"))
      (node (ref "U1") (pin "L16") (pinfunction "VCCINT_L16") (pintype "power_in"))
      (node (ref "U1") (pin "M11") (pinfunction "VCCINT_M11") (pintype "power_in"))
      (node (ref "U1") (pin "M13") (pinfunction "VCCINT_M13") (pintype "power_in"))
      (node (ref "U1") (pin "M15") (pinfunction "VCCINT_M15") (pintype "power_in"))
      (node (ref "U1") (pin "N12") (pinfunction "VCCINT_N12") (pintype "power_in"))
      (node (ref "U1") (pin "N14") (pinfunction "VCCINT_N14") (pintype "power_in"))
      (node (ref "U1") (pin "N16") (pinfunction "VCCINT_N16") (pintype "power_in"))
      (node (ref "U1") (pin "P11") (pinfunction "VCCINT_P11") (pintype "power_in"))
      (node (ref "U1") (pin "P13") (pinfunction "VCCINT_P13") (pintype "power_in"))
      (node (ref "U1") (pin "P15") (pinfunction "VCCINT_P15") (pintype "power_in"))
      (node (ref "U1") (pin "R12") (pinfunction "VCCINT_R12") (pintype "power_in"))
      (node (ref "U1") (pin "R14") (pinfunction "VCCINT_R14") (pintype "power_in"))
      (node (ref "U1") (pin "R16") (pinfunction "VCCINT_R16") (pintype "power_in"))
      (node (ref "U1") (pin "T11") (pinfunction "VCCINT_T11") (pintype "power_in"))
      (node (ref "U1") (pin "T13") (pinfunction "VCCINT_T13") (pintype "power_in"))
      (node (ref "U1") (pin "T15") (pinfunction "VCCINT_T15") (pintype "power_in"))
      (node (ref "U1") (pin "T17") (pinfunction "VCCINT_T17") (pintype "power_in"))
      (node (ref "U1") (pin "U10") (pinfunction "VCCINT_U10") (pintype "power_in"))
      (node (ref "U1") (pin "U16") (pinfunction "VCCINT_U16") (pintype "power_in"))
    )
    (net (code "2") (name "+2V5") (class "Default")
      (node (ref "C261") (pin "1") (pinfunction "1_1") (pintype "passive"))
      (node (ref "C262") (pin "1") (pinfunction "1_1") (pintype "passive"))
      (node (ref "C263") (pin "1") (pinfunction "1_1") (pintype "passive"))
      (node (ref "C264") (pin "1") (pinfunction "1_1") (pintype "passive"))
      (node (ref "C265") (pin "1") (pinfunction "1_1") (pintype "passive"))
      (node (ref "C266") (pin "1") (pinfunction "1_1") (pintype "passive"))
      (node (ref "C267") (pin "1") (pinfunction "1_1") (pintype "passive"))
      (node (ref "C361") (pin "1") (pinfunction "1_1") (pintype "passive"))
      (node (ref "C362") (pin "1") (pinfunction "1_1") (pintype "passive"))
      (node (ref "C363") (pin "1") (pinfunction "1_1") (pintype "passive"))
      (node (ref "C364") (pin "1") (pinfunction "1_1") (pintype "passive"))
      (node (ref "C365") (pin "1") (pinfunction "1_1") (pintype "passive"))
      (node (ref "C461") (pin "1") (pinfunction "1_1") (pintype "passive"))
      (node (ref "U1") (pin "AA10") (pinfunction "VCCAUX_AA10") (pintype "power_in"))
      (node (ref "U1") (pin "AA16") (pinfunction "VCCAUX_AA16") (pintype "power_in"))
      (node (ref "U1") (pin "AA21") (pinfunction "VCCAUX_AA21") (pintype "power_in"))
      (node (ref "U1") (pin "AA6") (pinfunction "VCCAUX_AA6") (pintype "power_in"))
      (node (ref "U1") (pin "F21") (pinfunction "VCCAUX_F21") (pintype "power_in"))
      (node (ref "U1") (pin "F6") (pinfunction "VCCAUX_F6") (pintype "power_in"))
      (node (ref "U1") (pin "G12") (pinfunction "VCCAUX_G12") (pintype "power_in"))
      (node (ref "U1") (pin "G15") (pinfunction "VCCAUX_G15") (pintype "power_in"))
      (node (ref "U1") (pin "J18") (pinfunction "VCCAUX_J18") (pintype "power_in"))
      (node (ref "U1") (pin "J9") (pinfunction "VCCAUX_J9") (pintype "power_in"))
      (node (ref "U1") (pin "K13") (pinfunction "VCCAUX_K13") (pintype "power_in"))
      (node (ref "U1") (pin "L22") (pinfunction "VCCAUX_L22") (pintype "power_in"))
      (node (ref "U1") (pin "L5") (pinfunction "VCCAUX_L5") (pintype "power_in"))
      (node (ref "U1") (pin "M17") (pinfunction "VCCAUX_M17") (pintype "power_in"))
      (node (ref "U1") (pin "N10") (pinfunction "VCCAUX_N10") (pintype "power_in"))
      (node (ref "U1") (pin "U14") (pinfunction "VCCAUX_U14") (pintype "power_in"))
      (node (ref "U1") (pin "U6") (pinfunction "VCCAUX_U6") (pintype "power_in"))
      (node (ref "U1") (pin "V9") (pinfunction "VCCAUX_V9") (pintype "power_in"))
      (node (ref "U1") (pin "Y19") (pinfunction "VCCAUX_Y19") (pintype "power_in"))
    )
    (net (code "3") (name "+3V3") (class "Default")
      (node (ref "C201") (pin "1") (pinfunction "1_1") (pintype "passive"))
      (node (ref "C202") (pin "1") (pinfunction "1_1") (pintype "passive"))
      (node (ref "C203") (pin "1") (pinfunction "1_1") (pintype "passive"))
      (node (ref "C204") (pin "1") (pinfunction "1_1") (pintype "passive"))
      (node (ref "C205") (pin "1") (pinfunction "1_1") (pintype "passive"))
      (node (ref "C211") (pin "1") (pinfunction "1_1") (pintype "passive"))
      (node (ref "C212") (pin "1") (pinfunction "1_1") (pintype "passive"))
      (node (ref "C213") (pin "1") (pinfunction "1_1") (pintype "passive"))
      (node (ref "C214") (pin "1") (pinfunction "1_1") (pintype "passive"))
      (node (ref "C215") (pin "1") (pinfunction "1_1") (pintype "passive"))
      (node (ref "C221") (pin "1") (pinfunction "1_1") (pintype "passive"))
      (node (ref "C222") (pin "1") (pinfunction "1_1") (pintype "passive"))
      (node (ref "C223") (pin "1") (pinfunction "1_1") (pintype "passive"))
      (node (ref "C224") (pin "1") (pinfunction "1_1") (pintype "passive"))
      (node (ref "C225") (pin "1") (pinfunction "1_1") (pintype "passive"))
      (node (ref "C231") (pin "1") (pinfunction "1_1") (pintype "passive"))
      (node (ref "C232") (pin "1") (pinfunction "1_1") (pintype "passive"))
      (node (ref "C233") (pin "1") (pinfunction "1_1") (pintype "passive"))
      (node (ref "C234") (pin "1") (pinfunction "1_1") (pintype "passive"))
      (node (ref "C235") (pin "1") (pinfunction "1_1") (pintype "passive"))
      (node (ref "C241") (pin "1") (pinfunction "1_1") (pintype "passive"))
      (node (ref "C242") (pin "1") (pinfunction "1_1") (pintype "passive"))
      (node (ref "C243") (pin "1") (pinfunction "1_1") (pintype "passive"))
      (node (ref "C244") (pin "1") (pinfunction "1_1") (pintype "passive"))
      (node (ref "C245") (pin "1") (pinfunction "1_1") (pintype "passive"))
      (node (ref "C251") (pin "1") (pinfunction "1_1") (pintype "passive"))
      (node (ref "C252") (pin "1") (pinfunction "1_1") (pintype "passive"))
      (node (ref "C253") (pin "1") (pinfunction "1_1") (pintype "passive"))
      (node (ref "C254") (pin "1") (pinfunction "1_1") (pintype "passive"))
      (node (ref "C255") (pin "1") (pinfunction "1_1") (pintype "passive"))
      (node (ref "C301") (pin "1") (pinfunction "1_1") (pintype "passive"))
      (node (ref "C302") (pin "1") (pinfunction "1_1") (pintype "passive"))
      (node (ref "C311") (pin "1") (pinfunction "1_1") (pintype "passive"))
      (node (ref "C312") (pin "1") (pinfunction "1_1") (pintype "passive"))
      (node (ref "C313") (pin "1") (pinfunction "1_1") (pintype "passive"))
      (node (ref "C321") (pin "1") (pinfunction "1_1") (pintype "passive"))
      (node (ref "C322") (pin "1") (pinfunction "1_1") (pintype "passive"))
      (node (ref "C331") (pin "1") (pinfunction "1_1") (pintype "passive"))
      (node (ref "C332") (pin "1") (pinfunction "1_1") (pintype "passive"))
      (node (ref "C341") (pin "1") (pinfunction "1_1") (pintype "passive"))
      (node (ref "C342") (pin "1") (pinfunction "1_1") (pintype "passive"))
      (node (ref "C351") (pin "1") (pinfunction "1_1") (pintype "passive"))
      (node (ref "C401") (pin "1") (pinfunction "1_1") (pintype "passive"))
      (node (ref "C411") (pin "1") (pinfunction "1_1") (pintype "passive"))
      (node (ref "C421") (pin "1") (pinfunction "1_1") (pintype "passive"))
      (node (ref "C431") (pin "1") (pinfunction "1_1") (pintype "passive"))
      (node (ref "C441") (pin "1") (pinfunction "1_1") (pintype "passive"))
      (node (ref "C451") (pin "1") (pinfunction "1_1") (pintype "passive"))
      (node (ref "U1") (pin "AB14") (pinfunction "VCCO_2_AB14") (pintype "power_in"))
      (node (ref "U1") (pin "AB23") (pinfunction "VCCO_1_AB23") (pintype "power_in"))
      (node (ref "U1") (pin "AC10") (pinfunction "VCCO_2_AC10") (pintype "power_in"))
      (node (ref "U1") (pin "AC18") (pinfunction "VCCO_2_AC18") (pintype "power_in"))
      (node (ref "U1") (pin "AC21") (pinfunction "VCCO_2_AC21") (pintype "power_in"))
      (node (ref "U1") (pin "AC6") (pinfunction "VCCO_3_AC6") (pintype "power_in"))
      (node (ref "U1") (pin "AD2") (pinfunction "VCCO_3_AD2") (pintype "power_in"))
      (node (ref "U1") (pin "AD25") (pinfunction "VCCO_1_AD25") (pintype "power_in"))
      (node (ref "U1") (pin "AE12") (pinfunction "VCCO_2_AE12") (pintype "power_in"))
      (node (ref "U1") (pin "AE16") (pinfunction "VCCO_2_AE16") (pintype "power_in"))
      (node (ref "U1") (pin "AE20") (pinfunction "VCCO_2_AE20") (pintype "power_in"))
      (node (ref "U1") (pin "AE8") (pinfunction "VCCO_2_AE8") (pintype "power_in"))
      (node (ref "U1") (pin "B11") (pinfunction "VCCO_0_B11") (pintype "power_in"))
      (node (ref "U1") (pin "B15") (pinfunction "VCCO_0_B15") (pintype "power_in"))
      (node (ref "U1") (pin "B19") (pinfunction "VCCO_0_B19") (pintype "power_in"))
      (node (ref "U1") (pin "B3") (pinfunction "VCCO_0_B3") (pintype "power_in"))
      (node (ref "U1") (pin "B7") (pinfunction "VCCO_0_B7") (pintype "power_in"))
      (node (ref "U1") (pin "C22") (pinfunction "VCCO_0_C22") (pintype "power_in"))
      (node (ref "U1") (pin "D17") (pinfunction "VCCO_0_D17") (pintype "power_in"))
      (node (ref "U1") (pin "D2") (pinfunction "VCCO_4_D2") (pintype "power_in"))
      (node (ref "U1") (pin "D25") (pinfunction "VCCO_5_D25") (pintype "power_in"))
      (node (ref "U1") (pin "D9") (pinfunction "VCCO_0_D9") (pintype "power_in"))
      (node (ref "U1") (pin "E13") (pinfunction "VCCO_0_E13") (pintype "power_in"))
      (node (ref "U1") (pin "F23") (pinfunction "VCCO_5_F23") (pintype "power_in"))
      (node (ref "U1") (pin "F4") (pinfunction "VCCO_4_F4") (pintype "power_in"))
      (node (ref "U1") (pin "G10") (pinfunction "VCCO_0_G10") (pintype "power_in"))
      (node (ref "U1") (pin "G18") (pinfunction "VCCO_0_G18") (pintype "power_in"))
      (node (ref "U1") (pin "H14") (pinfunction "VCCO_0_H14") (pintype "power_in"))
      (node (ref "U1") (pin "H2") (pinfunction "VCCO_4_H2") (pintype "power_in"))
      (node (ref "U1") (pin "H25") (pinfunction "VCCO_5_H25") (pintype "power_in"))
      (node (ref "U1") (pin "J21") (pinfunction "VCCO_5_J21") (pintype "power_in"))
      (node (ref "U1") (pin "J6") (pinfunction "VCCO_4_J6") (pintype "power_in"))
      (node (ref "U1") (pin "K23") (pinfunction "VCCO_5_K23") (pintype "power_in"))
      (node (ref "U1") (pin "K4") (pinfunction "VCCO_4_K4") (pintype "power_in"))
      (node (ref "U1") (pin "M2") (pinfunction "VCCO_4_M2") (pintype "power_in"))
      (node (ref "U1") (pin "M20") (pinfunction "VCCO_1_M20") (pintype "power_in"))
      (node (ref "U1") (pin "M25") (pinfunction "VCCO_5_M25") (pintype "power_in"))
      (node (ref "U1") (pin "M7") (pinfunction "VCCO_3_M7") (pintype "power_in"))
      (node (ref "U1") (pin "P23") (pinfunction "VCCO_1_P23") (pintype "power_in"))
      (node (ref "U1") (pin "P4") (pinfunction "VCCO_3_P4") (pintype "power_in"))
      (node (ref "U1") (pin "P9") (pinfunction "VCCO_3_P9") (pintype "power_in"))
      (node (ref "U1") (pin "T2") (pinfunction "VCCO_3_T2") (pintype "power_in"))
      (node (ref "U1") (pin "T25") (pinfunction "VCCO_1_T25") (pintype "power_in"))
      (node (ref "U1") (pin "T7") (pinfunction "VCCO_3_T7") (pintype "power_in"))
      (node (ref "U1") (pin "U18") (pinfunction "VCCO_1_U18") (pintype "power_in"))
      (node (ref "U1") (pin "V21") (pinfunction "VCCO_1_V21") (pintype "power_in"))
      (node (ref "U1") (pin "W23") (pinfunction "VCCO_1_W23") (pintype "power_in"))
      (node (ref "U1") (pin "W4") (pinfunction "VCCO_3_W4") (pintype "power_in"))
      (node (ref "U1") (pin "W6") (pinfunction "VCCO_3_W6") (pintype "power_in"))
      (node (ref "U1") (pin "Y12") (pinfunction "VCCO_2_Y12") (pintype "power_in"))
      (node (ref "U1") (pin "Y17") (pinfunction "VCCO_2_Y17") (pintype "power_in"))
      (node (ref "U1") (pin "Y2") (pinfunction "VCCO_3_Y2") (pintype "power_in"))
      (node (ref "U1") (pin "Y25") (pinfunction "VCCO_1_Y25") (pintype "power_in"))
    )
    (net (code "4") (name "GND") (class "Default")
      (node (ref "C201") (pin "2") (pinfunction "2_2") (pintype "passive"))
      (node (ref "C202") (pin "2") (pinfunction "2_2") (pintype "passive"))
      (node (ref "C203") (pin "2") (pinfunction "2_2") (pintype "passive"))
      (node (ref "C204") (pin "2") (pinfunction "2_2") (pintype "passive"))
      (node (ref "C205") (pin "2") (pinfunction "2_2") (pintype "passive"))
      (node (ref "C211") (pin "2") (pinfunction "2_2") (pintype "passive"))
      (node (ref "C212") (pin "2") (pinfunction "2_2") (pintype "passive"))
      (node (ref "C213") (pin "2") (pinfunction "2_2") (pintype "passive"))
      (node (ref "C214") (pin "2") (pinfunction "2_2") (pintype "passive"))
      (node (ref "C215") (pin "2") (pinfunction "2_2") (pintype "passive"))
      (node (ref "C221") (pin "2") (pinfunction "2_2") (pintype "passive"))
      (node (ref "C222") (pin "2") (pinfunction "2_2") (pintype "passive"))
      (node (ref "C223") (pin "2") (pinfunction "2_2") (pintype "passive"))
      (node (ref "C224") (pin "2") (pinfunction "2_2") (pintype "passive"))
      (node (ref "C225") (pin "2") (pinfunction "2_2") (pintype "passive"))
      (node (ref "C231") (pin "2") (pinfunction "2_2") (pintype "passive"))
      (node (ref "C232") (pin "2") (pinfunction "2_2") (pintype "passive"))
      (node (ref "C233") (pin "2") (pinfunction "2_2") (pintype "passive"))
      (node (ref "C234") (pin "2") (pinfunction "2_2") (pintype "passive"))
      (node (ref "C235") (pin "2") (pinfunction "2_2") (pintype "passive"))
      (node (ref "C241") (pin "2") (pinfunction "2_2") (pintype "passive"))
      (node (ref "C242") (pin "2") (pinfunction "2_2") (pintype "passive"))
      (node (ref "C243") (pin "2") (pinfunction "2_2") (pintype "passive"))
      (node (ref "C244") (pin "2") (pinfunction "2_2") (pintype "passive"))
      (node (ref "C245") (pin "2") (pinfunction "2_2") (pintype "passive"))
      (node (ref "C251") (pin "2") (pinfunction "2_2") (pintype "passive"))
      (node (ref "C252") (pin "2") (pinfunction "2_2") (pintype "passive"))
      (node (ref "C253") (pin "2") (pinfunction "2_2") (pintype "passive"))
      (node (ref "C254") (pin "2") (pinfunction "2_2") (pintype "passive"))
      (node (ref "C255") (pin "2") (pinfunction "2_2") (pintype "passive"))
      (node (ref "C261") (pin "2") (pinfunction "2_2") (pintype "passive"))
      (node (ref "C262") (pin "2") (pinfunction "2_2") (pintype "passive"))
      (node (ref "C263") (pin "2") (pinfunction "2_2") (pintype "passive"))
      (node (ref "C264") (pin "2") (pinfunction "2_2") (pintype "passive"))
      (node (ref "C265") (pin "2") (pinfunction "2_2") (pintype "passive"))
      (node (ref "C266") (pin "2") (pinfunction "2_2") (pintype "passive"))
      (node (ref "C267") (pin "2") (pinfunction "2_2") (pintype "passive"))
      (node (ref "C271") (pin "2") (pinfunction "2_2") (pintype "passive"))
      (node (ref "C272") (pin "2") (pinfunction "2_2") (pintype "passive"))
      (node (ref "C273") (pin "2") (pinfunction "2_2") (pintype "passive"))
      (node (ref "C274") (pin "2") (pinfunction "2_2") (pintype "passive"))
      (node (ref "C275") (pin "2") (pinfunction "2_2") (pintype "passive"))
      (node (ref "C276") (pin "2") (pinfunction "2_2") (pintype "passive"))
      (node (ref "C277") (pin "2") (pinfunction "2_2") (pintype "passive"))
      (node (ref "C301") (pin "2") (pinfunction "2_2") (pintype "passive"))
      (node (ref "C302") (pin "2") (pinfunction "2_2") (pintype "passive"))
      (node (ref "C311") (pin "2") (pinfunction "2_2") (pintype "passive"))
      (node (ref "C312") (pin "2") (pinfunction "2_2") (pintype "passive"))
      (node (ref "C313") (pin "2") (pinfunction "2_2") (pintype "passive"))
      (node (ref "C321") (pin "2") (pinfunction "2_2") (pintype "passive"))
      (node (ref "C322") (pin "2") (pinfunction "2_2") (pintype "passive"))
      (node (ref "C331") (pin "2") (pinfunction "2_2") (pintype "passive"))
      (node (ref "C332") (pin "2") (pinfunction "2_2") (pintype "passive"))
      (node (ref "C341") (pin "2") (pinfunction "2_2") (pintype "passive"))
      (node (ref "C342") (pin "2") (pinfunction "2_2") (pintype "passive"))
      (node (ref "C351") (pin "2") (pinfunction "2_2") (pintype "passive"))
      (node (ref "C361") (pin "2") (pinfunction "2_2") (pintype "passive"))
      (node (ref "C362") (pin "2") (pinfunction "2_2") (pintype "passive"))
      (node (ref "C363") (pin "2") (pinfunction "2_2") (pintype "passive"))
      (node (ref "C364") (pin "2") (pinfunction "2_2") (pintype "passive"))
      (node (ref "C365") (pin "2") (pinfunction "2_2") (pintype "passive"))
      (node (ref "C371") (pin "2") (pinfunction "2_2") (pintype "passive"))
      (node (ref "C372") (pin "2") (pinfunction "2_2") (pintype "passive"))
      (node (ref "C375") (pin "2") (pinfunction "2_2") (pintype "passive"))
      (node (ref "C401") (pin "2") (pinfunction "2_2") (pintype "passive"))
      (node (ref "C411") (pin "2") (pinfunction "2_2") (pintype "passive"))
      (node (ref "C421") (pin "2") (pinfunction "2_2") (pintype "passive"))
      (node (ref "C431") (pin "2") (pinfunction "2_2") (pintype "passive"))
      (node (ref "C441") (pin "2") (pinfunction "2_2") (pintype "passive"))
      (node (ref "C451") (pin "2") (pinfunction "2_2") (pintype "passive"))
      (node (ref "C461") (pin "2") (pinfunction "2_2") (pintype "passive"))
      (node (ref "C471") (pin "2") (pinfunction "2_2") (pintype "passive"))
    )
    (net (code "5") (name "unconnected-(U1H-VBATT-PadW21)") (class "Default")
      (node (ref "U1") (pin "W21") (pinfunction "VBATT_W21") (pintype "power_in"))
    )
  )
)
